# kd_inz_mems.net
KiCad netlist of a schematic drawn in Altium Designer
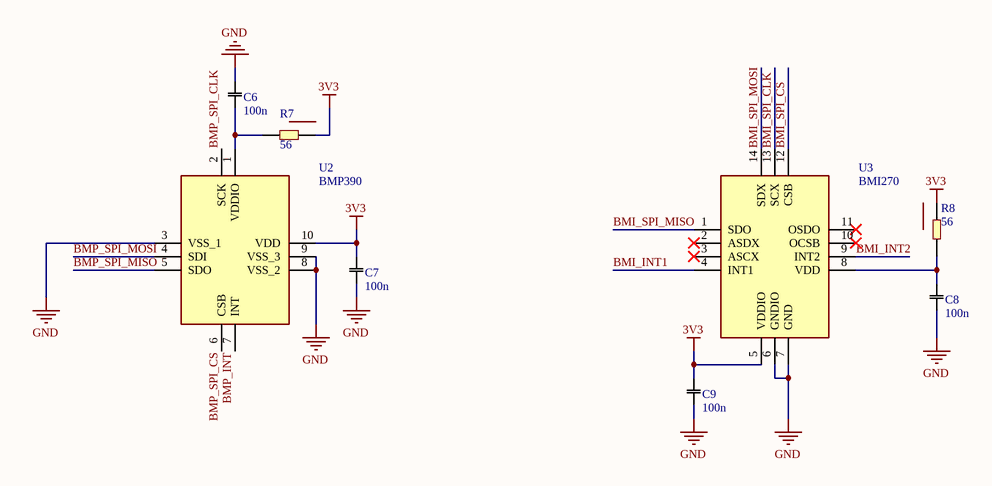
[diagram p0: kd_inz_mems.SchDoc]

(export (version "E")
  (design (tool "Eeschema 10.0.6"))
  (components
    (comp (ref "C6")
      (value "100n")
      (footprint "0402")
      (description "Capacitor")
      (libsource (lib "basic_lib_v1-2") (part "C"))
    )
    (comp (ref "C7")
      (value "100n")
      (footprint "0402")
      (description "Capacitor")
      (libsource (lib "basic_lib_v1-2") (part "C"))
    )
    (comp (ref "C8")
      (value "100n")
      (footprint "0402")
      (description "Capacitor")
      (libsource (lib "basic_lib_v1-2") (part "C"))
    )
    (comp (ref "C9")
      (value "100n")
      (footprint "0402")
      (description "Capacitor")
      (libsource (lib "basic_lib_v1-2") (part "C"))
    )
    (comp (ref "R7")
      (value "56")
      (footprint "0402")
      (description "Resistor")
      (libsource (lib "basic_lib_v1-2") (part "R"))
    )
    (comp (ref "R8")
      (value "56")
      (footprint "0402")
      (description "Resistor")
      (libsource (lib "") (part "R_1"))
    )
    (comp (ref "U2")
      (value "BMP390")
      (footprint "kd_lib:BMP390")
      (description "Integrated Circuit")
      (fields (field (name "MOUSER PART NUMBER") "262-BMP390"))
      (libsource (lib "kd_lib") (part "BMP390"))
    )
    (comp (ref "U3")
      (value "BMI270")
      (footprint "kd_lib:QFN50P300X250X87-14N")
      (description "Integrated Circuit")
      (fields (field (name "MOUSER PART NUMBER") "262-BMI270"))
      (libsource (lib "kd_lib") (part "BMI270"))
    )
  )
  (nets
    (net (code "1") (name "/BMI_INT1") (class "Default")
      (node (ref "U3") (pin "4") (pinfunction "INT1_4") (pintype "passive"))
    )
    (net (code "2") (name "/BMI_INT2") (class "Default")
      (node (ref "U3") (pin "9") (pinfunction "INT2_9") (pintype "passive"))
    )
    (net (code "3") (name "/BMI_SPI_CLK") (class "Default")
      (node (ref "U3") (pin "13") (pinfunction "SCX_13") (pintype "passive"))
    )
    (net (code "4") (name "/BMI_SPI_CS") (class "Default")
      (node (ref "U3") (pin "12") (pinfunction "CSB_12") (pintype "passive"))
    )
    (net (code "5") (name "/BMI_SPI_MISO") (class "Default")
      (node (ref "U3") (pin "1") (pinfunction "SDO_1") (pintype "passive"))
    )
    (net (code "6") (name "/BMI_SPI_MOSI") (class "Default")
      (node (ref "U3") (pin "14") (pinfunction "SDX_14") (pintype "passive"))
    )
    (net (code "7") (name "/BMP_INT") (class "Default")
      (node (ref "U2") (pin "7") (pinfunction "INT_7") (pintype "passive"))
    )
    (net (code "8") (name "/BMP_SPI_CLK") (class "Default")
      (node (ref "U2") (pin "2") (pinfunction "SCK_2") (pintype "passive"))
    )
    (net (code "9") (name "/BMP_SPI_CS") (class "Default")
      (node (ref "U2") (pin "6") (pinfunction "CSB_6") (pintype "passive"))
    )
    (net (code "10") (name "/BMP_SPI_MISO") (class "Default")
      (node (ref "U2") (pin "5") (pinfunction "SDO_5") (pintype "passive"))
    )
    (net (code "11") (name "/BMP_SPI_MOSI") (class "Default")
      (node (ref "U2") (pin "4") (pinfunction "SDI_4") (pintype "passive"))
    )
    (net (code "12") (name "3V3") (class "Default")
      (node (ref "C7") (pin "2") (pintype "passive"))
      (node (ref "C9") (pin "2") (pintype "passive"))
      (node (ref "R7") (pin "2") (pintype "passive"))
      (node (ref "R8") (pin "2") (pintype "passive"))
      (node (ref "U2") (pin "10") (pinfunction "VDD_10") (pintype "passive"))
      (node (ref "U3") (pin "5") (pinfunction "VDDIO_5") (pintype "passive"))
    )
    (net (code "13") (name "GND") (class "Default")
      (node (ref "C6") (pin "2") (pintype "passive"))
      (node (ref "C7") (pin "1") (pintype "passive"))
      (node (ref "C8") (pin "1") (pintype "passive"))
      (node (ref "C9") (pin "1") (pintype "passive"))
      (node (ref "U2") (pin "3") (pinfunction "VSS_1_3") (pintype "passive"))
      (node (ref "U2") (pin "8") (pinfunction "VSS_2_8") (pintype "passive"))
      (node (ref "U2") (pin "9") (pinfunction "VSS_3_9") (pintype "passive"))
      (node (ref "U3") (pin "6") (pinfunction "GNDIO_6") (pintype "passive"))
      (node (ref "U3") (pin "7") (pinfunction "GND_7") (pintype "passive"))
    )
    (net (code "14") (name "Net-(U2-VDDIO)") (class "Default")
      (node (ref "C6") (pin "1") (pintype "passive"))
      (node (ref "R7") (pin "1") (pintype "passive"))
      (node (ref "U2") (pin "1") (pinfunction "VDDIO_1") (pintype "passive"))
    )
    (net (code "15") (name "Net-(U3-VDD)") (class "Default")
      (node (ref "C8") (pin "2") (pintype "passive"))
      (node (ref "R8") (pin "1") (pintype "passive"))
      (node (ref "U3") (pin "8") (pinfunction "VDD_8") (pintype "passive"))
    )
    (net (code "16") (name "unconnected-(U3-ASCX-Pad3)") (class "Default")
      (node (ref "U3") (pin "3") (pinfunction "ASCX_3") (pintype "passive+no_connect"))
    )
    (net (code "17") (name "unconnected-(U3-ASDX-Pad2)") (class "Default")
      (node (ref "U3") (pin "2") (pinfunction "ASDX_2") (pintype "passive+no_connect"))
    )
    (net (code "18") (name "unconnected-(U3-OCSB-Pad10)") (class "Default")
      (node (ref "U3") (pin "10") (pinfunction "OCSB_10") (pintype "passive+no_connect"))
    )
    (net (code "19") (name "unconnected-(U3-OSDO-Pad11)") (class "Default")
      (node (ref "U3") (pin "11") (pinfunction "OSDO_11") (pintype "passive+no_connect"))
    )
  )
)
